# esp01_flasher.net
KiCad netlist of a schematic drawn in EAGLE
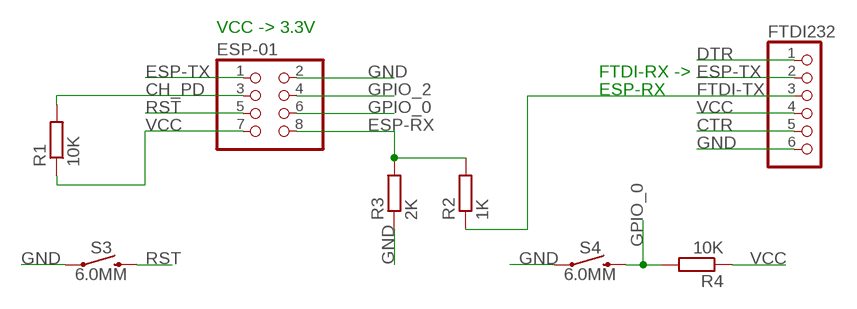
[diagram p0: schematic, sheet 1]

(export (version "E")
  (design (tool "Eeschema 10.0.6"))
  (components
    (comp (ref "ESP-01")
      (value "PINHD-2X4")
      (footprint "eagle-import:2X04")
      (libsource (lib "eagle-import") (part "PINHD-2X4"))
    )
    (comp (ref "FTDI232")
      (value "PINHD-1X6")
      (footprint "eagle-import:1X06")
      (libsource (lib "eagle-import") (part "PINHD-1X6"))
    )
    (comp (ref "R1")
      (value "10K")
      (footprint "eagle-import:R1206")
      (libsource (lib "eagle-import") (part "RESISTOR-1206"))
    )
    (comp (ref "R2")
      (value "1K")
      (footprint "eagle-import:R1206")
      (libsource (lib "eagle-import") (part "RESISTOR-1206"))
    )
    (comp (ref "R3")
      (value "2K")
      (footprint "eagle-import:R1206")
      (libsource (lib "eagle-import") (part "RESISTOR-1206"))
    )
    (comp (ref "R4")
      (value "10K")
      (footprint "eagle-import:R1206")
      (libsource (lib "eagle-import") (part "RESISTOR-1206"))
    )
    (comp (ref "S3")
      (value "6.0MM")
      (footprint "eagle-import:TACTILE_SWITCH_PTH_6.0MM")
      (libsource (lib "eagle-import") (part "MOMENTARY-SWITCH-SPST-PTH-6.0MM"))
    )
    (comp (ref "S4")
      (value "6.0MM")
      (footprint "eagle-import:TACTILE_SWITCH_PTH_6.0MM")
      (libsource (lib "eagle-import") (part "MOMENTARY-SWITCH-SPST-PTH-6.0MM"))
    )
  )
  (nets
    (net (code "1") (name "/CH_PD") (class "Default")
      (node (ref "ESP-01") (pin "3") (pinfunction "3_3") (pintype "passive"))
      (node (ref "R1") (pin "2") (pinfunction "2_2") (pintype "passive"))
    )
    (net (code "2") (name "/CTR") (class "Default")
      (node (ref "FTDI232") (pin "5") (pinfunction "5_5") (pintype "passive"))
    )
    (net (code "3") (name "/DTR") (class "Default")
      (node (ref "FTDI232") (pin "1") (pinfunction "1_1") (pintype "passive"))
    )
    (net (code "4") (name "/ESP-RX") (class "Default")
      (node (ref "ESP-01") (pin "8") (pinfunction "8_8") (pintype "passive"))
      (node (ref "R2") (pin "2") (pinfunction "2_2") (pintype "passive"))
      (node (ref "R3") (pin "2") (pinfunction "2_2") (pintype "passive"))
    )
    (net (code "5") (name "/ESP-TX") (class "Default")
      (node (ref "ESP-01") (pin "1") (pinfunction "1_1") (pintype "passive"))
      (node (ref "FTDI232") (pin "2") (pinfunction "2_2") (pintype "passive"))
    )
    (net (code "6") (name "/FTDI-TX") (class "Default")
      (node (ref "FTDI232") (pin "3") (pinfunction "3_3") (pintype "passive"))
      (node (ref "R2") (pin "1") (pinfunction "1_1") (pintype "passive"))
    )
    (net (code "7") (name "/GND") (class "Default")
      (node (ref "ESP-01") (pin "2") (pinfunction "2_2") (pintype "passive"))
      (node (ref "FTDI232") (pin "6") (pinfunction "6_6") (pintype "passive"))
      (node (ref "R3") (pin "1") (pinfunction "1_1") (pintype "passive"))
      (node (ref "S3") (pin "1") (pinfunction "1_1") (pintype "passive"))
      (node (ref "S4") (pin "1") (pinfunction "1_1") (pintype "passive"))
    )
    (net (code "8") (name "/GPIO_0") (class "Default")
      (node (ref "ESP-01") (pin "6") (pinfunction "6_6") (pintype "passive"))
      (node (ref "R4") (pin "2") (pinfunction "2_2") (pintype "passive"))
      (node (ref "S4") (pin "3") (pinfunction "2_3") (pintype "passive"))
    )
    (net (code "9") (name "/GPIO_2") (class "Default")
      (node (ref "ESP-01") (pin "4") (pinfunction "4_4") (pintype "passive"))
    )
    (net (code "10") (name "/RST") (class "Default")
      (node (ref "ESP-01") (pin "5") (pinfunction "5_5") (pintype "passive"))
      (node (ref "S3") (pin "3") (pinfunction "2_3") (pintype "passive"))
    )
    (net (code "11") (name "/VCC") (class "Default")
      (node (ref "ESP-01") (pin "7") (pinfunction "7_7") (pintype "passive"))
      (node (ref "FTDI232") (pin "4") (pinfunction "4_4") (pintype "passive"))
      (node (ref "R1") (pin "1") (pinfunction "1_1") (pintype "passive"))
      (node (ref "R4") (pin "1") (pinfunction "1_1") (pintype "passive"))
    )
  )
)
